# Grove_-_IR_distance_interrupter.net
KiCad netlist of a schematic drawn in EAGLE
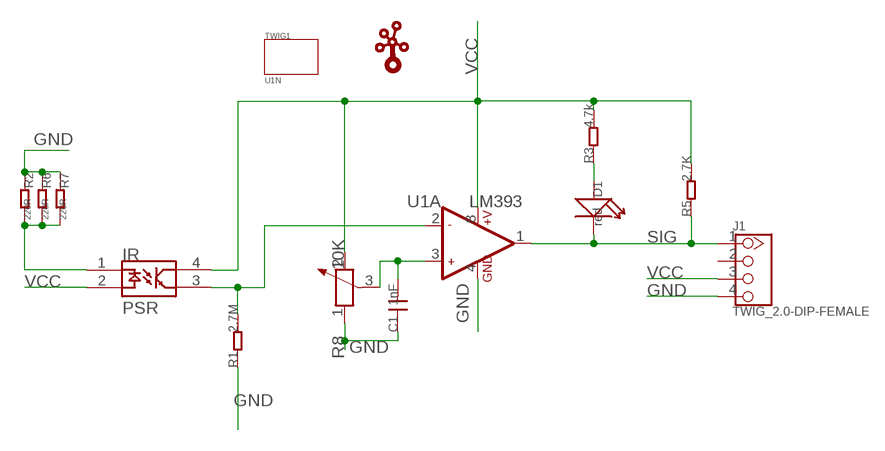
[diagram p0: schematic, sheet 1]

(export (version "E")
  (design (tool "Eeschema 10.0.6"))
  (components
    (comp (ref "C1")
      (value "1nF")
      (footprint "eagle-import:0603")
      (libsource (lib "eagle-import") (part "C-0603"))
    )
    (comp (ref "D1")
      (value "red")
      (footprint "eagle-import:LED0603")
      (libsource (lib "eagle-import") (part "007-LED3540"))
    )
    (comp (ref "J1")
      (value "TWIG_2.0-DIP-FEMALE")
      (footprint "eagle-import:2.0_1X4")
      (libsource (lib "eagle-import") (part "TWIG_2.0-DIP-FEMALE"))
    )
    (comp (ref "PSR")
      (value "PSR")
      (footprint "eagle-import:PSR")
      (libsource (lib "eagle-import") (part "PSR"))
    )
    (comp (ref "R1")
      (value "2.7M")
      (footprint "eagle-import:0603_S")
      (libsource (lib "eagle-import") (part "005-R0603_S"))
    )
    (comp (ref "R2")
      (value "220R")
      (footprint "eagle-import:0805")
      (libsource (lib "eagle-import") (part "R-0805"))
    )
    (comp (ref "R3")
      (value "4.7k")
      (footprint "eagle-import:0603_S")
      (libsource (lib "eagle-import") (part "005-R0603_S"))
    )
    (comp (ref "R5")
      (value "2.7K")
      (footprint "eagle-import:0603_S")
      (libsource (lib "eagle-import") (part "005-R0603_S"))
    )
    (comp (ref "R6")
      (value "220R")
      (footprint "eagle-import:0805")
      (libsource (lib "eagle-import") (part "R-0805"))
    )
    (comp (ref "R7")
      (value "220R")
      (footprint "eagle-import:0805")
      (libsource (lib "eagle-import") (part "R-0805"))
    )
    (comp (ref "R8")
      (value "10K")
      (footprint "eagle-import:3P-SQUA-7X6.8")
      (libsource (lib "eagle-import") (part "R-POTENTIOMETER'3362'"))
    )
    (comp (ref "TWIG1")
      (value "U1N")
      (footprint "eagle-import:U1N")
      (libsource (lib "eagle-import") (part "U1N"))
    )
    (comp (ref "U$2")
      (value "TWIGLOGOTWIGLOGO_SMALL")
      (footprint "eagle-import:TWIGLOGO_SMALL")
      (libsource (lib "eagle-import") (part "TWIGLOGOTWIGLOGO_SMALL"))
    )
    (comp (ref "U1")
      (value "LM393")
      (footprint "eagle-import:SO08")
      (libsource (lib "eagle-import") (part "LMV358"))
    )
  )
  (nets
    (net (code "1") (name "/GND") (class "Default")
      (node (ref "C1") (pin "1") (pinfunction "1_1") (pintype "passive"))
      (node (ref "J1") (pin "4") (pinfunction "4_4") (pintype "bidirectional"))
      (node (ref "R1") (pin "1") (pinfunction "1_1") (pintype "passive"))
      (node (ref "R2") (pin "1") (pinfunction "1_1") (pintype "passive"))
      (node (ref "R6") (pin "1") (pinfunction "1_1") (pintype "passive"))
      (node (ref "R7") (pin "1") (pinfunction "1_1") (pintype "passive"))
      (node (ref "R8") (pin "1") (pinfunction "1_1") (pintype "passive"))
      (node (ref "U1") (pin "4") (pinfunction "GND_4") (pintype "power_in"))
    )
    (net (code "2") (name "/SIG") (class "Default")
      (node (ref "D1") (pin "2") (pinfunction "-_2") (pintype "passive"))
      (node (ref "J1") (pin "1") (pinfunction "1_1") (pintype "bidirectional"))
      (node (ref "R5") (pin "1") (pinfunction "1_1") (pintype "passive"))
      (node (ref "U1") (pin "1") (pinfunction "OUT1_1") (pintype "output"))
    )
    (net (code "3") (name "/VCC") (class "Default")
      (node (ref "J1") (pin "3") (pinfunction "3_3") (pintype "bidirectional"))
      (node (ref "PSR") (pin "2") (pinfunction "2_2") (pintype "bidirectional"))
      (node (ref "PSR") (pin "4") (pinfunction "4_4") (pintype "bidirectional"))
      (node (ref "R3") (pin "2") (pinfunction "2_2") (pintype "passive"))
      (node (ref "R5") (pin "2") (pinfunction "2_2") (pintype "passive"))
      (node (ref "R8") (pin "2") (pinfunction "2_2") (pintype "passive"))
      (node (ref "U1") (pin "8") (pinfunction "+V_8") (pintype "power_in"))
    )
    (net (code "4") (name "Net-(D1-+)") (class "Default")
      (node (ref "D1") (pin "1") (pinfunction "+_1") (pintype "passive"))
      (node (ref "R3") (pin "1") (pinfunction "1_1") (pintype "passive"))
    )
    (net (code "5") (name "Net-(PSR-Pad1)") (class "Default")
      (node (ref "PSR") (pin "1") (pinfunction "1_1") (pintype "bidirectional"))
      (node (ref "R2") (pin "2") (pinfunction "2_2") (pintype "passive"))
      (node (ref "R6") (pin "2") (pinfunction "2_2") (pintype "passive"))
      (node (ref "R7") (pin "2") (pinfunction "2_2") (pintype "passive"))
    )
    (net (code "6") (name "Net-(U1A-+IN1)") (class "Default")
      (node (ref "C1") (pin "2") (pinfunction "2_2") (pintype "passive"))
      (node (ref "R8") (pin "3") (pinfunction "3_3") (pintype "passive"))
      (node (ref "U1") (pin "3") (pinfunction "+IN1_3") (pintype "input"))
    )
    (net (code "7") (name "Net-(U1A--IN1)") (class "Default")
      (node (ref "PSR") (pin "3") (pinfunction "3_3") (pintype "bidirectional"))
      (node (ref "R1") (pin "2") (pinfunction "2_2") (pintype "passive"))
      (node (ref "U1") (pin "2") (pinfunction "-IN1_2") (pintype "input"))
    )
    (net (code "8") (name "unconnected-(J1-Pad2)") (class "Default")
      (node (ref "J1") (pin "2") (pinfunction "2_2") (pintype "bidirectional"))
    )
  )
)
